# T01_Synth_Glove_Prototype_Board.net
KiCad netlist of a schematic drawn in EAGLE
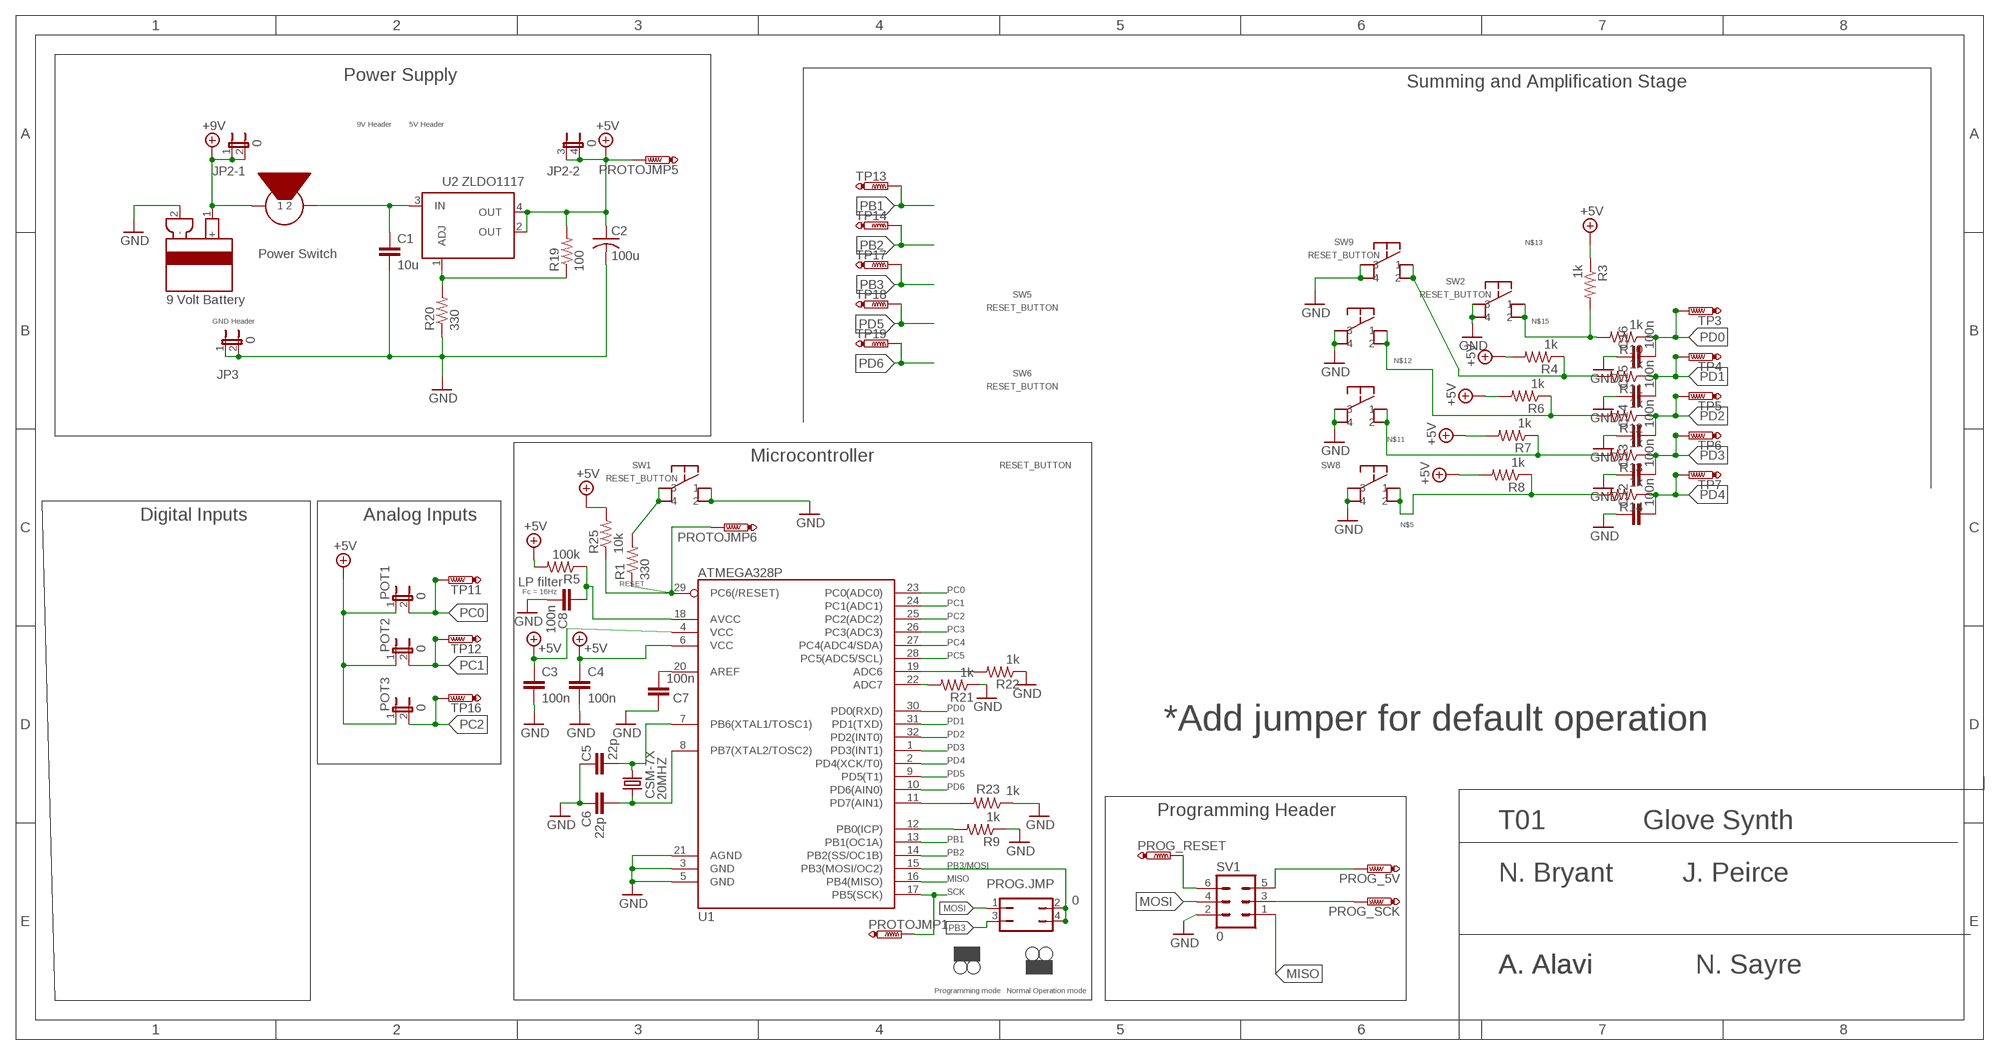
[diagram p0: schematic, sheet 1]

(export (version "E")
  (design (tool "Eeschema 10.0.6"))
  (components
    (comp (ref "20MHZ")
      (value "CSM-7X")
      (footprint "eagle-import:CSM-7X-DU")
      (libsource (lib "eagle-import") (part "CSM-7X-DU"))
    )
    (comp (ref "C1")
      (value "10u")
      (footprint "eagle-import:0603-CAP")
      (libsource (lib "eagle-import") (part "CAP0603-CAP"))
    )
    (comp (ref "C2")
      (value "100u")
      (footprint "eagle-import:C075-042X103")
      (libsource (lib "eagle-import") (part "C-US075-042X103"))
    )
    (comp (ref "C3")
      (value "100n")
      (footprint "eagle-import:0603-CAP")
      (libsource (lib "eagle-import") (part "CAP0603-CAP"))
    )
    (comp (ref "C4")
      (value "100n")
      (footprint "eagle-import:0603-CAP")
      (libsource (lib "eagle-import") (part "CAP0603-CAP"))
    )
    (comp (ref "C5")
      (value "22p")
      (footprint "eagle-import:0603-CAP")
      (libsource (lib "eagle-import") (part "CAP0603-CAP"))
    )
    (comp (ref "C6")
      (value "22p")
      (footprint "eagle-import:0603-CAP")
      (libsource (lib "eagle-import") (part "CAP0603-CAP"))
    )
    (comp (ref "C7")
      (value "100n")
      (footprint "eagle-import:0603-CAP")
      (libsource (lib "eagle-import") (part "CAP0603-CAP"))
    )
    (comp (ref "C8")
      (value "100n")
      (footprint "eagle-import:0603-CAP")
      (libsource (lib "eagle-import") (part "CAP0603-CAP"))
    )
    (comp (ref "C12")
      (value "100n")
      (footprint "eagle-import:0603-CAP")
      (libsource (lib "eagle-import") (part "CAP0603-CAP"))
    )
    (comp (ref "C13")
      (value "100n")
      (footprint "eagle-import:0603-CAP")
      (libsource (lib "eagle-import") (part "CAP0603-CAP"))
    )
    (comp (ref "C14")
      (value "100n")
      (footprint "eagle-import:0603-CAP")
      (libsource (lib "eagle-import") (part "CAP0603-CAP"))
    )
    (comp (ref "C15")
      (value "100n")
      (footprint "eagle-import:0603-CAP")
      (libsource (lib "eagle-import") (part "CAP0603-CAP"))
    )
    (comp (ref "C16")
      (value "100n")
      (footprint "eagle-import:0603-CAP")
      (libsource (lib "eagle-import") (part "CAP0603-CAP"))
    )
    (comp (ref "JP2")
      (value "0")
      (footprint "eagle-import:JP2Q")
      (libsource (lib "eagle-import") (part "JP2QE"))
    )
    (comp (ref "JP3")
      (value "0")
      (footprint "eagle-import:JP1")
      (libsource (lib "eagle-import") (part "JP1E"))
    )
    (comp (ref "POT1")
      (value "0")
      (footprint "eagle-import:JP1")
      (libsource (lib "eagle-import") (part "JP1E"))
    )
    (comp (ref "POT2")
      (value "0")
      (footprint "eagle-import:JP1")
      (libsource (lib "eagle-import") (part "JP1E"))
    )
    (comp (ref "POT3")
      (value "0")
      (footprint "eagle-import:JP1")
      (libsource (lib "eagle-import") (part "JP1E"))
    )
    (comp (ref "PROG.JMP")
      (value "0")
      (footprint "eagle-import:JP2Q")
      (libsource (lib "eagle-import") (part "JP2Q"))
    )
    (comp (ref "PROG_5V")
      (value "PTR1B2,54")
      (footprint "eagle-import:B2,54")
      (libsource (lib "eagle-import") (part "PTR1B2,54"))
    )
    (comp (ref "PROG_RESET")
      (value "PTR1B2,54")
      (footprint "eagle-import:B2,54")
      (libsource (lib "eagle-import") (part "PTR1B2,54"))
    )
    (comp (ref "PROG_SCK")
      (value "PTR1B2,54")
      (footprint "eagle-import:B2,54")
      (libsource (lib "eagle-import") (part "PTR1B2,54"))
    )
    (comp (ref "PROTOJMP1")
      (value "PTR1B2,54")
      (footprint "eagle-import:B2,54")
      (libsource (lib "eagle-import") (part "PTR1B2,54"))
    )
    (comp (ref "PROTOJMP5")
      (value "PTR1B2,54")
      (footprint "eagle-import:B2,54")
      (libsource (lib "eagle-import") (part "PTR1B2,54"))
    )
    (comp (ref "PROTOJMP6")
      (value "PTR1B2,54")
      (footprint "eagle-import:B2,54")
      (libsource (lib "eagle-import") (part "PTR1B2,54"))
    )
    (comp (ref "R1")
      (value "330")
      (footprint "eagle-import:0603-RES")
      (libsource (lib "eagle-import") (part "RESISTOR0603"))
    )
    (comp (ref "R3")
      (value "1k")
      (footprint "eagle-import:0603-RES")
      (libsource (lib "eagle-import") (part "RESISTOR0603"))
    )
    (comp (ref "R4")
      (value "1k")
      (footprint "eagle-import:0603-RES")
      (libsource (lib "eagle-import") (part "RESISTOR0603"))
    )
    (comp (ref "R5")
      (value "100k")
      (footprint "eagle-import:0603-RES")
      (libsource (lib "eagle-import") (part "RESISTOR0603"))
    )
    (comp (ref "R6")
      (value "1k")
      (footprint "eagle-import:0603-RES")
      (libsource (lib "eagle-import") (part "RESISTOR0603"))
    )
    (comp (ref "R7")
      (value "1k")
      (footprint "eagle-import:0603-RES")
      (libsource (lib "eagle-import") (part "RESISTOR0603"))
    )
    (comp (ref "R8")
      (value "1k")
      (footprint "eagle-import:0603-RES")
      (libsource (lib "eagle-import") (part "RESISTOR0603"))
    )
    (comp (ref "R9")
      (value "1k")
      (footprint "eagle-import:0603-RES")
      (libsource (lib "eagle-import") (part "RESISTOR0603"))
    )
    (comp (ref "R10")
      (value "1k")
      (footprint "eagle-import:0603-RES")
      (libsource (lib "eagle-import") (part "RESISTOR0603"))
    )
    (comp (ref "R11")
      (value "1k")
      (footprint "eagle-import:0603-RES")
      (libsource (lib "eagle-import") (part "RESISTOR0603"))
    )
    (comp (ref "R12")
      (value "1k")
      (footprint "eagle-import:0603-RES")
      (libsource (lib "eagle-import") (part "RESISTOR0603"))
    )
    (comp (ref "R13")
      (value "1k")
      (footprint "eagle-import:0603-RES")
      (libsource (lib "eagle-import") (part "RESISTOR0603"))
    )
    (comp (ref "R14")
      (value "1k")
      (footprint "eagle-import:0603-RES")
      (libsource (lib "eagle-import") (part "RESISTOR0603"))
    )
    (comp (ref "R19")
      (value "100")
      (footprint "eagle-import:0603-RES")
      (libsource (lib "eagle-import") (part "RESISTOR0603"))
    )
    (comp (ref "R20")
      (value "330")
      (footprint "eagle-import:0603-RES")
      (libsource (lib "eagle-import") (part "RESISTOR0603"))
    )
    (comp (ref "R21")
      (value "1k")
      (footprint "eagle-import:0603-RES")
      (libsource (lib "eagle-import") (part "RESISTOR0603"))
    )
    (comp (ref "R22")
      (value "1k")
      (footprint "eagle-import:0603-RES")
      (libsource (lib "eagle-import") (part "RESISTOR0603"))
    )
    (comp (ref "R23")
      (value "1k")
      (footprint "eagle-import:0603-RES")
      (libsource (lib "eagle-import") (part "RESISTOR0603"))
    )
    (comp (ref "R25")
      (value "10k")
      (footprint "eagle-import:0603-RES")
      (libsource (lib "eagle-import") (part "RESISTOR0603"))
    )
    (comp (ref "SV1")
      (value "0")
      (footprint "eagle-import:MA03-2")
      (libsource (lib "eagle-import") (part "MA03-2"))
    )
    (comp (ref "SW1")
      (value "RESET_BUTTON")
      (footprint "eagle-import:RESET_BUTTON")
      (libsource (lib "eagle-import") (part "RESET_BUTTON"))
    )
    (comp (ref "SW2")
      (value "RESET_BUTTON")
      (footprint "eagle-import:RESET_BUTTON")
      (libsource (lib "eagle-import") (part "RESET_BUTTON"))
    )
    (comp (ref "SW5")
      (value "RESET_BUTTON")
      (footprint "eagle-import:RESET_BUTTON")
      (libsource (lib "eagle-import") (part "RESET_BUTTON"))
    )
    (comp (ref "SW6")
      (value "RESET_BUTTON")
      (footprint "eagle-import:RESET_BUTTON")
      (libsource (lib "eagle-import") (part "RESET_BUTTON"))
    )
    (comp (ref "SW8")
      (value "RESET_BUTTON")
      (footprint "eagle-import:RESET_BUTTON")
      (libsource (lib "eagle-import") (part "RESET_BUTTON"))
    )
    (comp (ref "SW9")
      (value "RESET_BUTTON")
      (footprint "eagle-import:RESET_BUTTON")
      (libsource (lib "eagle-import") (part "RESET_BUTTON"))
    )
    (comp (ref "TP3")
      (value "PTR1B2,54")
      (footprint "eagle-import:B2,54")
      (libsource (lib "eagle-import") (part "PTR1B2,54"))
    )
    (comp (ref "TP4")
      (value "PTR1B2,54")
      (footprint "eagle-import:B2,54")
      (libsource (lib "eagle-import") (part "PTR1B2,54"))
    )
    (comp (ref "TP5")
      (value "PTR1B2,54")
      (footprint "eagle-import:B2,54")
      (libsource (lib "eagle-import") (part "PTR1B2,54"))
    )
    (comp (ref "TP6")
      (value "PTR1B2,54")
      (footprint "eagle-import:B2,54")
      (libsource (lib "eagle-import") (part "PTR1B2,54"))
    )
    (comp (ref "TP7")
      (value "PTR1B2,54")
      (footprint "eagle-import:B2,54")
      (libsource (lib "eagle-import") (part "PTR1B2,54"))
    )
    (comp (ref "TP11")
      (value "PTR1B2,54")
      (footprint "eagle-import:B2,54")
      (libsource (lib "eagle-import") (part "PTR1B2,54"))
    )
    (comp (ref "TP12")
      (value "PTR1B2,54")
      (footprint "eagle-import:B2,54")
      (libsource (lib "eagle-import") (part "PTR1B2,54"))
    )
    (comp (ref "TP13")
      (value "PTR1B2,54")
      (footprint "eagle-import:B2,54")
      (libsource (lib "eagle-import") (part "PTR1B2,54"))
    )
    (comp (ref "TP14")
      (value "PTR1B2,54")
      (footprint "eagle-import:B2,54")
      (libsource (lib "eagle-import") (part "PTR1B2,54"))
    )
    (comp (ref "TP16")
      (value "PTR1B2,54")
      (footprint "eagle-import:B2,54")
      (libsource (lib "eagle-import") (part "PTR1B2,54"))
    )
    (comp (ref "TP17")
      (value "PTR1B2,54")
      (footprint "eagle-import:B2,54")
      (libsource (lib "eagle-import") (part "PTR1B2,54"))
    )
    (comp (ref "TP18")
      (value "PTR1B2,54")
      (footprint "eagle-import:B2,54")
      (libsource (lib "eagle-import") (part "PTR1B2,54"))
    )
    (comp (ref "TP19")
      (value "PTR1B2,54")
      (footprint "eagle-import:B2,54")
      (libsource (lib "eagle-import") (part "PTR1B2,54"))
    )
    (comp (ref "U$7")
      (value "POWER_SWITCH")
      (footprint "eagle-import:JP1")
      (libsource (lib "eagle-import") (part "POWER_SWITCH"))
    )
    (comp (ref "U$8")
      (value "9VOLTBATTERY")
      (footprint "eagle-import:JP1")
      (libsource (lib "eagle-import") (part "9VOLTBATTERY"))
    )
    (comp (ref "U1")
      (value "ATMEGA328P")
      (footprint "eagle-import:TQFP32-08")
      (libsource (lib "eagle-import") (part "ATMEGA328_SMT"))
    )
    (comp (ref "U2")
      (value "ZLDO1117")
      (footprint "eagle-import:SOT223")
      (libsource (lib "eagle-import") (part "ZLDO1117"))
    )
  )
  (nets
    (net (code "1") (name "+5V") (class "Default")
      (node (ref "C2") (pin "1") (pinfunction "1_1") (pintype "passive"))
      (node (ref "C3") (pin "1") (pinfunction "1_1") (pintype "passive"))
      (node (ref "C4") (pin "1") (pinfunction "1_1") (pintype "passive"))
      (node (ref "JP2") (pin "3") (pinfunction "1_3") (pintype "passive"))
      (node (ref "JP2") (pin "4") (pinfunction "2_4") (pintype "passive"))
      (node (ref "POT1") (pin "1") (pinfunction "1_1") (pintype "passive"))
      (node (ref "POT2") (pin "1") (pinfunction "1_1") (pintype "passive"))
      (node (ref "POT3") (pin "1") (pinfunction "1_1") (pintype "passive"))
      (node (ref "PROTOJMP5") (pin "TP") (pinfunction "TP_TP") (pintype "input"))
      (node (ref "R19") (pin "2") (pinfunction "2_2") (pintype "passive"))
      (node (ref "R25") (pin "2") (pinfunction "2_2") (pintype "passive"))
      (node (ref "R3") (pin "1") (pinfunction "1_1") (pintype "passive"))
      (node (ref "R4") (pin "2") (pinfunction "2_2") (pintype "passive"))
      (node (ref "R5") (pin "2") (pinfunction "2_2") (pintype "passive"))
      (node (ref "R6") (pin "2") (pinfunction "2_2") (pintype "passive"))
      (node (ref "R7") (pin "2") (pinfunction "2_2") (pintype "passive"))
      (node (ref "R8") (pin "2") (pinfunction "2_2") (pintype "passive"))
      (node (ref "U1") (pin "4") (pinfunction "VCC_4") (pintype "bidirectional"))
      (node (ref "U1") (pin "6") (pinfunction "VCC_6") (pintype "bidirectional"))
      (node (ref "U2") (pin "2") (pinfunction "OUT_2") (pintype "bidirectional"))
      (node (ref "U2") (pin "4") (pinfunction "OUT_4") (pintype "bidirectional"))
    )
    (net (code "2") (name "+9V") (class "Default")
      (node (ref "JP2") (pin "1") (pinfunction "1_1") (pintype "passive"))
      (node (ref "JP2") (pin "2") (pinfunction "2_2") (pintype "passive"))
      (node (ref "U$7") (pin "1") (pinfunction "1_1") (pintype "bidirectional"))
      (node (ref "U$8") (pin "1") (pinfunction "+_1") (pintype "bidirectional"))
    )
    (net (code "3") (name "/N$5") (class "Default")
      (node (ref "R14") (pin "2") (pinfunction "2_2") (pintype "passive"))
      (node (ref "R8") (pin "1") (pinfunction "1_1") (pintype "passive"))
      (node (ref "SW8") (pin "1") (pinfunction "1_1") (pintype "bidirectional"))
      (node (ref "SW8") (pin "2") (pinfunction "2_2") (pintype "bidirectional"))
    )
    (net (code "4") (name "/N$11") (class "Default")
      (node (ref "R13") (pin "2") (pinfunction "2_2") (pintype "passive"))
      (node (ref "R7") (pin "1") (pinfunction "1_1") (pintype "passive"))
      (node (ref "SW6") (pin "1") (pinfunction "1_1") (pintype "bidirectional"))
      (node (ref "SW6") (pin "2") (pinfunction "2_2") (pintype "bidirectional"))
    )
    (net (code "5") (name "/N$12") (class "Default")
      (node (ref "R12") (pin "2") (pinfunction "2_2") (pintype "passive"))
      (node (ref "R6") (pin "1") (pinfunction "1_1") (pintype "passive"))
      (node (ref "SW5") (pin "1") (pinfunction "1_1") (pintype "bidirectional"))
      (node (ref "SW5") (pin "2") (pinfunction "2_2") (pintype "bidirectional"))
    )
    (net (code "6") (name "/N$13") (class "Default")
      (node (ref "R11") (pin "2") (pinfunction "2_2") (pintype "passive"))
      (node (ref "R4") (pin "1") (pinfunction "1_1") (pintype "passive"))
      (node (ref "SW9") (pin "1") (pinfunction "1_1") (pintype "bidirectional"))
      (node (ref "SW9") (pin "2") (pinfunction "2_2") (pintype "bidirectional"))
    )
    (net (code "7") (name "/N$15") (class "Default")
      (node (ref "R10") (pin "2") (pinfunction "2_2") (pintype "passive"))
      (node (ref "R3") (pin "2") (pinfunction "2_2") (pintype "passive"))
      (node (ref "SW2") (pin "1") (pinfunction "1_1") (pintype "bidirectional"))
      (node (ref "SW2") (pin "2") (pinfunction "2_2") (pintype "bidirectional"))
    )
    (net (code "8") (name "/PB3{slash}MOSI") (class "Default")
      (node (ref "PROG.JMP") (pin "2") (pinfunction "2_2") (pintype "passive"))
      (node (ref "PROG.JMP") (pin "4") (pinfunction "4_4") (pintype "passive"))
      (node (ref "U1") (pin "15") (pinfunction "PB3(MOSI/OC2)_15") (pintype "bidirectional"))
    )
    (net (code "9") (name "/PC3") (class "Default")
      (node (ref "U1") (pin "26") (pinfunction "PC3(ADC3)_26") (pintype "bidirectional"))
    )
    (net (code "10") (name "/PC4") (class "Default")
      (node (ref "U1") (pin "27") (pinfunction "PC4(ADC4/SDA)_27") (pintype "bidirectional"))
    )
    (net (code "11") (name "/PC5") (class "Default")
      (node (ref "U1") (pin "28") (pinfunction "PC5(ADC5/SCL)_28") (pintype "bidirectional"))
    )
    (net (code "12") (name "/RESET") (class "Default")
      (node (ref "PROTOJMP6") (pin "TP") (pinfunction "TP_TP") (pintype "input"))
      (node (ref "R1") (pin "1") (pinfunction "1_1") (pintype "passive"))
      (node (ref "R25") (pin "1") (pinfunction "1_1") (pintype "passive"))
      (node (ref "U1") (pin "29") (pinfunction "PC6(/RESET)_29") (pintype "bidirectional"))
    )
    (net (code "13") (name "/SCK") (class "Default")
      (node (ref "PROTOJMP1") (pin "TP") (pinfunction "TP_TP") (pintype "input"))
      (node (ref "U1") (pin "17") (pinfunction "PB5(SCK)_17") (pintype "bidirectional"))
    )
    (net (code "14") (name "GND") (class "Default")
      (node (ref "C1") (pin "2") (pinfunction "2_2") (pintype "passive"))
      (node (ref "C12") (pin "1") (pinfunction "1_1") (pintype "passive"))
      (node (ref "C13") (pin "1") (pinfunction "1_1") (pintype "passive"))
      (node (ref "C14") (pin "1") (pinfunction "1_1") (pintype "passive"))
      (node (ref "C15") (pin "1") (pinfunction "1_1") (pintype "passive"))
      (node (ref "C16") (pin "1") (pinfunction "1_1") (pintype "passive"))
      (node (ref "C2") (pin "2") (pinfunction "2_2") (pintype "passive"))
      (node (ref "C3") (pin "2") (pinfunction "2_2") (pintype "passive"))
      (node (ref "C4") (pin "2") (pinfunction "2_2") (pintype "passive"))
      (node (ref "C5") (pin "2") (pinfunction "2_2") (pintype "passive"))
      (node (ref "C6") (pin "2") (pinfunction "2_2") (pintype "passive"))
      (node (ref "C7") (pin "2") (pinfunction "2_2") (pintype "passive"))
      (node (ref "C8") (pin "2") (pinfunction "2_2") (pintype "passive"))
      (node (ref "JP3") (pin "1") (pinfunction "1_1") (pintype "passive"))
      (node (ref "JP3") (pin "2") (pinfunction "2_2") (pintype "passive"))
      (node (ref "R20") (pin "1") (pinfunction "1_1") (pintype "passive"))
      (node (ref "R21") (pin "1") (pinfunction "1_1") (pintype "passive"))
      (node (ref "R22") (pin "1") (pinfunction "1_1") (pintype "passive"))
      (node (ref "R23") (pin "1") (pinfunction "1_1") (pintype "passive"))
      (node (ref "R9") (pin "1") (pinfunction "1_1") (pintype "passive"))
      (node (ref "SV1") (pin "2") (pinfunction "2_2") (pintype "passive"))
      (node (ref "SW1") (pin "1") (pinfunction "1_1") (pintype "bidirectional"))
      (node (ref "SW1") (pin "2") (pinfunction "2_2") (pintype "bidirectional"))
      (node (ref "SW2") (pin "3") (pinfunction "3_3") (pintype "bidirectional"))
      (node (ref "SW2") (pin "4") (pinfunction "4_4") (pintype "bidirectional"))
      (node (ref "SW5") (pin "3") (pinfunction "3_3") (pintype "bidirectional"))
      (node (ref "SW5") (pin "4") (pinfunction "4_4") (pintype "bidirectional"))
      (node (ref "SW6") (pin "3") (pinfunction "3_3") (pintype "bidirectional"))
      (node (ref "SW6") (pin "4") (pinfunction "4_4") (pintype "bidirectional"))
      (node (ref "SW8") (pin "3") (pinfunction "3_3") (pintype "bidirectional"))
      (node (ref "SW8") (pin "4") (pinfunction "4_4") (pintype "bidirectional"))
      (node (ref "SW9") (pin "3") (pinfunction "3_3") (pintype "bidirectional"))
      (node (ref "SW9") (pin "4") (pinfunction "4_4") (pintype "bidirectional"))
      (node (ref "U$8") (pin "2") (pinfunction "-_2") (pintype "bidirectional"))
      (node (ref "U1") (pin "21") (pinfunction "AGND_21") (pintype "bidirectional"))
      (node (ref "U1") (pin "3") (pinfunction "GND_3") (pintype "bidirectional"))
      (node (ref "U1") (pin "5") (pinfunction "GND_5") (pintype "bidirectional"))
    )
    (net (code "15") (name "MISO") (class "Default")
      (node (ref "SV1") (pin "1") (pinfunction "1_1") (pintype "passive"))
      (node (ref "U1") (pin "16") (pinfunction "PB4(MISO)_16") (pintype "bidirectional"))
    )
    (net (code "16") (name "MOSI") (class "Default")
      (node (ref "PROG.JMP") (pin "1") (pinfunction "1_1") (pintype "passive"))
      (node (ref "SV1") (pin "4") (pinfunction "4_4") (pintype "passive"))
    )
    (net (code "17") (name "Net-(PROG_5V-PadTP)") (class "Default")
      (node (ref "PROG_5V") (pin "TP") (pinfunction "TP_TP") (pintype "input"))
      (node (ref "SV1") (pin "5") (pinfunction "5_5") (pintype "passive"))
    )
    (net (code "18") (name "Net-(PROG_RESET-PadTP)") (class "Default")
      (node (ref "PROG_RESET") (pin "TP") (pinfunction "TP_TP") (pintype "input"))
      (node (ref "SV1") (pin "6") (pinfunction "6_6") (pintype "passive"))
    )
    (net (code "19") (name "Net-(PROG_SCK-PadTP)") (class "Default")
      (node (ref "PROG_SCK") (pin "TP") (pinfunction "TP_TP") (pintype "input"))
      (node (ref "SV1") (pin "3") (pinfunction "3_3") (pintype "passive"))
    )
    (net (code "20") (name "Net-(R1-Pad2)") (class "Default")
      (node (ref "R1") (pin "2") (pinfunction "2_2") (pintype "passive"))
      (node (ref "SW1") (pin "3") (pinfunction "3_3") (pintype "bidirectional"))
      (node (ref "SW1") (pin "4") (pinfunction "4_4") (pintype "bidirectional"))
    )
    (net (code "21") (name "Net-(U1-ADC6)") (class "Default")
      (node (ref "R22") (pin "2") (pinfunction "2_2") (pintype "passive"))
      (node (ref "U1") (pin "19") (pinfunction "ADC6_19") (pintype "bidirectional"))
    )
    (net (code "22") (name "Net-(U1-ADC7)") (class "Default")
      (node (ref "R21") (pin "2") (pinfunction "2_2") (pintype "passive"))
      (node (ref "U1") (pin "22") (pinfunction "ADC7_22") (pintype "bidirectional"))
    )
    (net (code "23") (name "Net-(U1-AREF)") (class "Default")
      (node (ref "C7") (pin "1") (pinfunction "1_1") (pintype "passive"))
      (node (ref "U1") (pin "20") (pinfunction "AREF_20") (pintype "bidirectional"))
    )
    (net (code "24") (name "Net-(U1-AVCC)") (class "Default")
      (node (ref "C8") (pin "1") (pinfunction "1_1") (pintype "passive"))
      (node (ref "R5") (pin "1") (pinfunction "1_1") (pintype "passive"))
      (node (ref "U1") (pin "18") (pinfunction "AVCC_18") (pintype "bidirectional"))
    )
    (net (code "25") (name "Net-(U1-PB0(ICP))") (class "Default")
      (node (ref "R9") (pin "2") (pinfunction "2_2") (pintype "passive"))
      (node (ref "U1") (pin "12") (pinfunction "PB0(ICP)_12") (pintype "bidirectional"))
    )
    (net (code "26") (name "Net-(U1-PB6(XTAL1{slash}TOSC1))") (class "Default")
      (node (ref "20MHZ") (pin "1") (pinfunction "1_1") (pintype "passive"))
      (node (ref "C5") (pin "1") (pinfunction "1_1") (pintype "passive"))
      (node (ref "U1") (pin "7") (pinfunction "PB6(XTAL1/TOSC1)_7") (pintype "bidirectional"))
    )
    (net (code "27") (name "Net-(U1-PB7(XTAL2{slash}TOSC2))") (class "Default")
      (node (ref "20MHZ") (pin "2") (pinfunction "2_2") (pintype "passive"))
      (node (ref "C6") (pin "1") (pinfunction "1_1") (pintype "passive"))
      (node (ref "U1") (pin "8") (pinfunction "PB7(XTAL2/TOSC2)_8") (pintype "bidirectional"))
    )
    (net (code "28") (name "Net-(U1-PD7(AIN1))") (class "Default")
      (node (ref "R23") (pin "2") (pinfunction "2_2") (pintype "passive"))
      (node (ref "U1") (pin "11") (pinfunction "PD7(AIN1)_11") (pintype "bidirectional"))
    )
    (net (code "29") (name "Net-(U2-ADJ)") (class "Default")
      (node (ref "R19") (pin "1") (pinfunction "1_1") (pintype "passive"))
      (node (ref "R20") (pin "2") (pinfunction "2_2") (pintype "passive"))
      (node (ref "U2") (pin "1") (pinfunction "ADJ_1") (pintype "bidirectional"))
    )
    (net (code "30") (name "Net-(U2-IN)") (class "Default")
      (node (ref "C1") (pin "1") (pinfunction "1_1") (pintype "passive"))
      (node (ref "U$7") (pin "2") (pinfunction "2_2") (pintype "bidirectional"))
      (node (ref "U2") (pin "3") (pinfunction "IN_3") (pintype "bidirectional"))
    )
    (net (code "31") (name "PB1") (class "Default")
      (node (ref "TP13") (pin "TP") (pinfunction "TP_TP") (pintype "input"))
      (node (ref "U1") (pin "13") (pinfunction "PB1(OC1A)_13") (pintype "bidirectional"))
    )
    (net (code "32") (name "PB2") (class "Default")
      (node (ref "TP14") (pin "TP") (pinfunction "TP_TP") (pintype "input"))
      (node (ref "U1") (pin "14") (pinfunction "PB2(SS/OC1B)_14") (pintype "bidirectional"))
    )
    (net (code "33") (name "PB3") (class "Default")
      (node (ref "PROG.JMP") (pin "3") (pinfunction "3_3") (pintype "passive"))
      (node (ref "TP17") (pin "TP") (pinfunction "TP_TP") (pintype "input"))
    )
    (net (code "34") (name "PC0") (class "Default")
      (node (ref "POT1") (pin "2") (pinfunction "2_2") (pintype "passive"))
      (node (ref "TP11") (pin "TP") (pinfunction "TP_TP") (pintype "input"))
      (node (ref "U1") (pin "23") (pinfunction "PC0(ADC0)_23") (pintype "bidirectional"))
    )
    (net (code "35") (name "PC1") (class "Default")
      (node (ref "POT2") (pin "2") (pinfunction "2_2") (pintype "passive"))
      (node (ref "TP12") (pin "TP") (pinfunction "TP_TP") (pintype "input"))
      (node (ref "U1") (pin "24") (pinfunction "PC1(ADC1)_24") (pintype "bidirectional"))
    )
    (net (code "36") (name "PC2") (class "Default")
      (node (ref "POT3") (pin "2") (pinfunction "2_2") (pintype "passive"))
      (node (ref "TP16") (pin "TP") (pinfunction "TP_TP") (pintype "input"))
      (node (ref "U1") (pin "25") (pinfunction "PC2(ADC2)_25") (pintype "bidirectional"))
    )
    (net (code "37") (name "PD0") (class "Default")
      (node (ref "C16") (pin "2") (pinfunction "2_2") (pintype "passive"))
      (node (ref "R10") (pin "1") (pinfunction "1_1") (pintype "passive"))
      (node (ref "TP3") (pin "TP") (pinfunction "TP_TP") (pintype "input"))
      (node (ref "U1") (pin "30") (pinfunction "PD0(RXD)_30") (pintype "bidirectional"))
    )
    (net (code "38") (name "PD1") (class "Default")
      (node (ref "C15") (pin "2") (pinfunction "2_2") (pintype "passive"))
      (node (ref "R11") (pin "1") (pinfunction "1_1") (pintype "passive"))
      (node (ref "TP4") (pin "TP") (pinfunction "TP_TP") (pintype "input"))
      (node (ref "U1") (pin "31") (pinfunction "PD1(TXD)_31") (pintype "bidirectional"))
    )
    (net (code "39") (name "PD2") (class "Default")
      (node (ref "C14") (pin "2") (pinfunction "2_2") (pintype "passive"))
      (node (ref "R12") (pin "1") (pinfunction "1_1") (pintype "passive"))
      (node (ref "TP5") (pin "TP") (pinfunction "TP_TP") (pintype "input"))
      (node (ref "U1") (pin "32") (pinfunction "PD2(INT0)_32") (pintype "bidirectional"))
    )
    (net (code "40") (name "PD3") (class "Default")
      (node (ref "C13") (pin "2") (pinfunction "2_2") (pintype "passive"))
      (node (ref "R13") (pin "1") (pinfunction "1_1") (pintype "passive"))
      (node (ref "TP6") (pin "TP") (pinfunction "TP_TP") (pintype "input"))
      (node (ref "U1") (pin "1") (pinfunction "PD3(INT1)_1") (pintype "bidirectional"))
    )
    (net (code "41") (name "PD4") (class "Default")
      (node (ref "C12") (pin "2") (pinfunction "2_2") (pintype "passive"))
      (node (ref "R14") (pin "1") (pinfunction "1_1") (pintype "passive"))
      (node (ref "TP7") (pin "TP") (pinfunction "TP_TP") (pintype "input"))
      (node (ref "U1") (pin "2") (pinfunction "PD4(XCK/T0)_2") (pintype "bidirectional"))
    )
    (net (code "42") (name "PD5") (class "Default")
      (node (ref "TP18") (pin "TP") (pinfunction "TP_TP") (pintype "input"))
      (node (ref "U1") (pin "9") (pinfunction "PD5(T1)_9") (pintype "bidirectional"))
    )
    (net (code "43") (name "PD6") (class "Default")
      (node (ref "TP19") (pin "TP") (pinfunction "TP_TP") (pintype "input"))
      (node (ref "U1") (pin "10") (pinfunction "PD6(AIN0)_10") (pintype "bidirectional"))
    )
  )
)
